# Schematic.net
KiCad netlist of a schematic drawn in Altium Designer
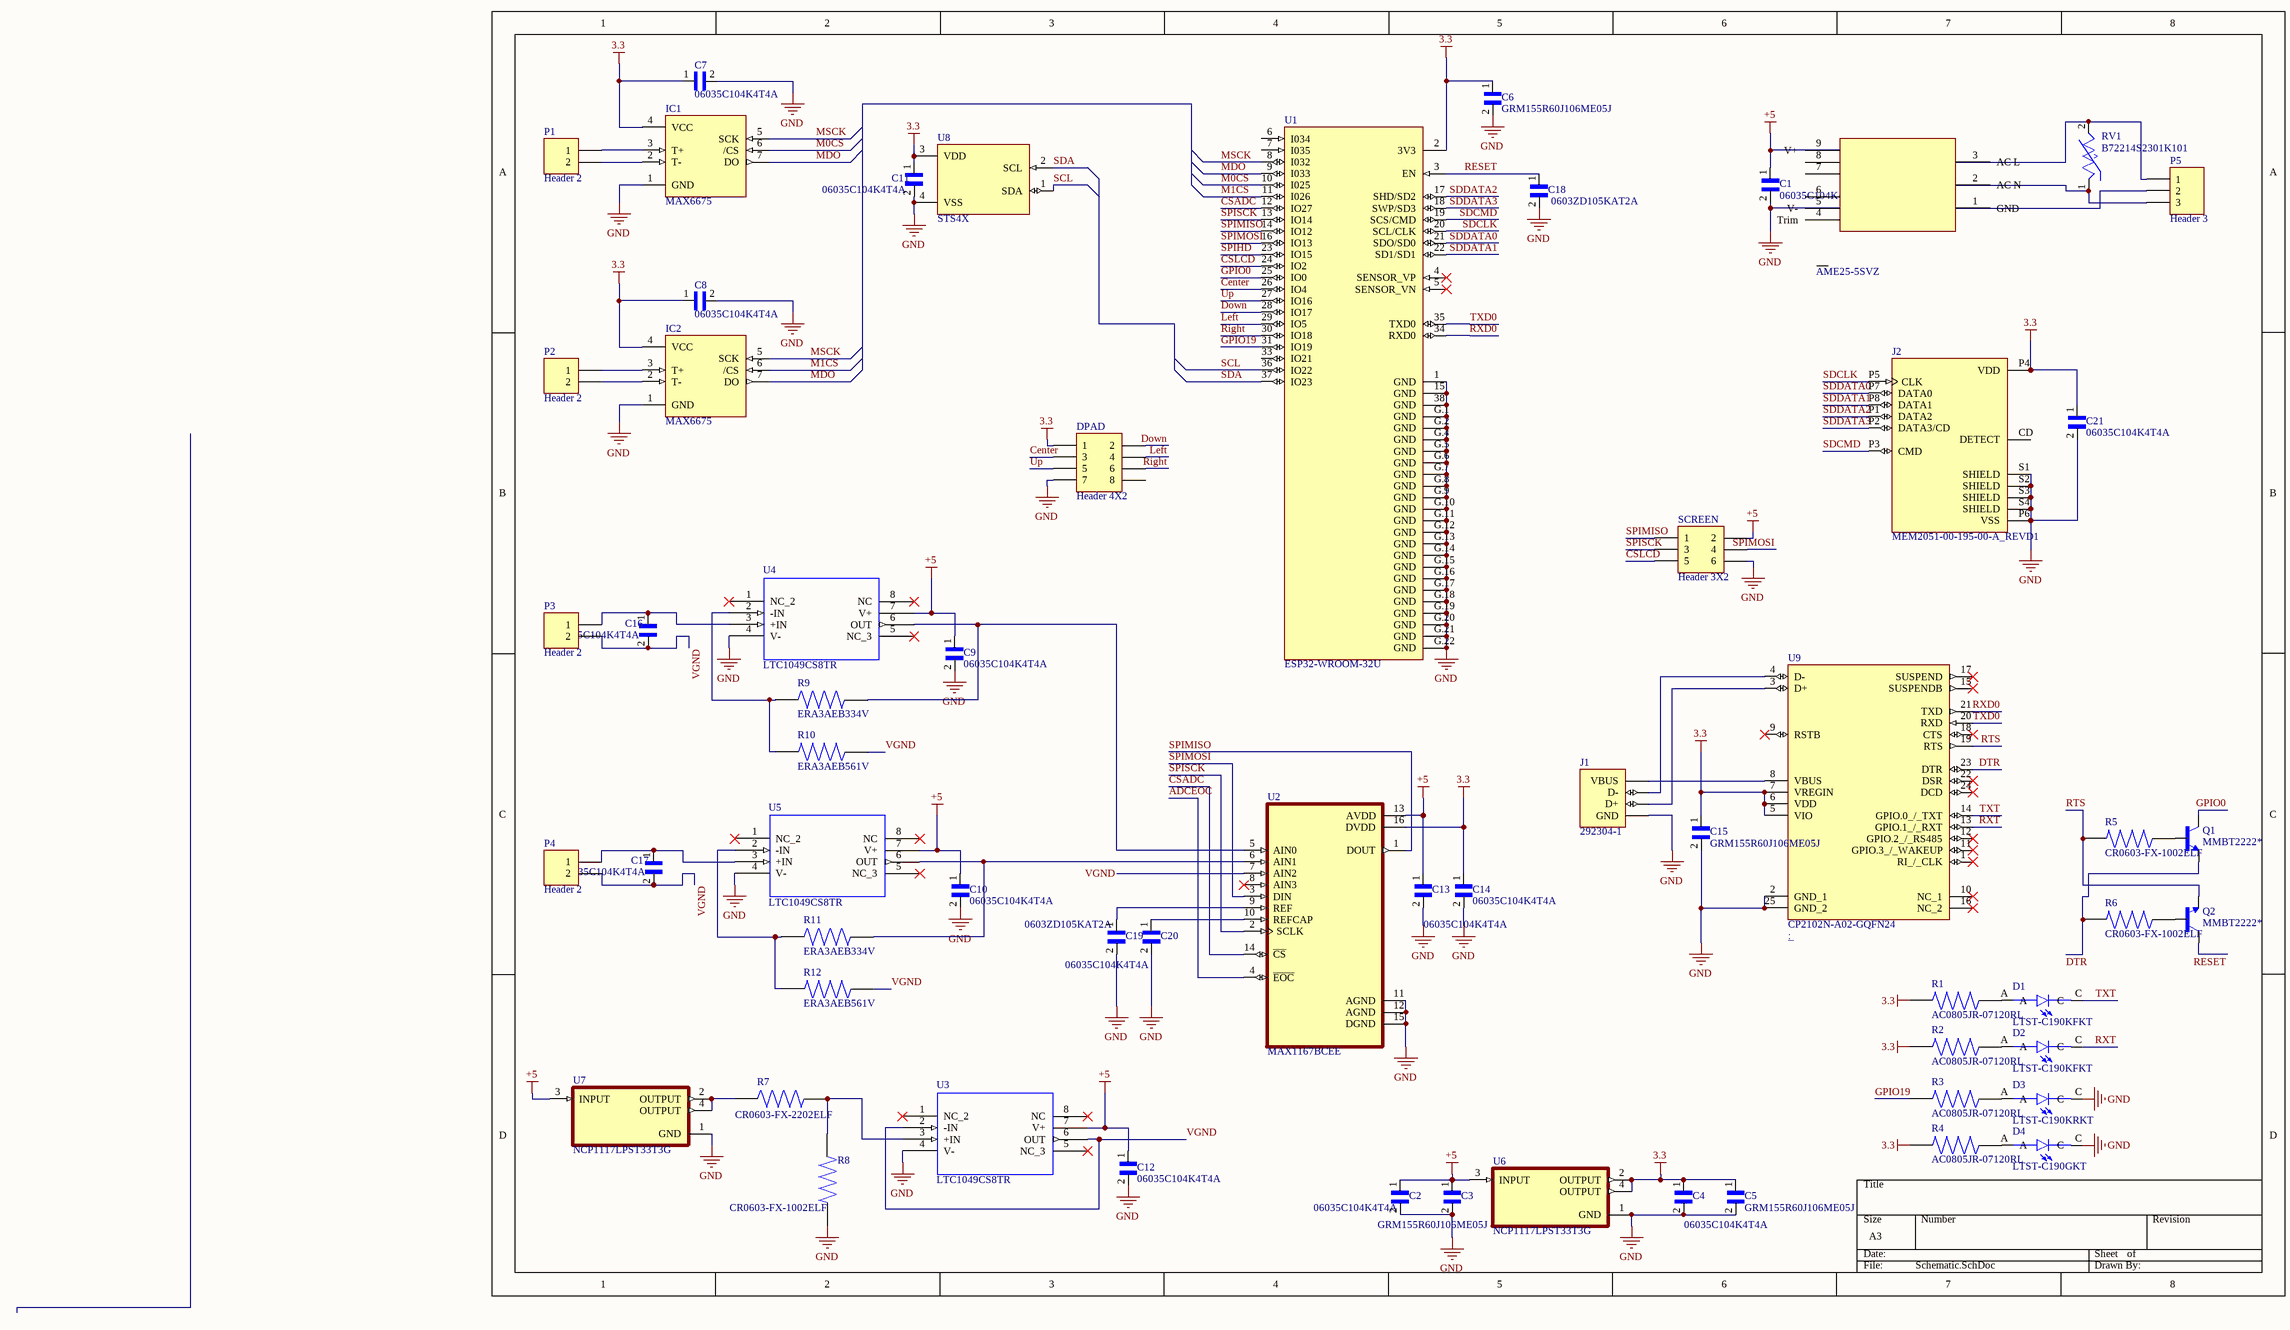
[diagram p0: Schematic.SchDoc]

(export (version "E")
  (design (tool "Eeschema 10.0.6"))
  (components
    (comp (ref "C1")
      (value "06035C104K4T4A")
      (footprint "CAPC1608X90N")
      (description "0.1ÂµF Â±10% 50V Ceramic Capacitor X7R 0603 _1608 Metric_")
      (fields (field (name "DIGI-KEY_PART_NUMBER") "478-9903-1-ND") (field (name "MF") "AVX"))
      (libsource (lib "06035C104K4T4A") (part "06035C104K4T4A"))
    )
    (comp (ref "C2")
      (value "06035C104K4T4A")
      (footprint "CAPC1608X90N")
      (description "0.1ÂµF Â±10% 50V Ceramic Capacitor X7R 0603 _1608 Metric_")
      (fields (field (name "DIGI-KEY_PART_NUMBER") "478-9903-1-ND") (field (name "MF") "AVX"))
      (libsource (lib "06035C104K4T4A") (part "06035C104K4T4A"))
    )
    (comp (ref "C3")
      (value "GRM155R60J106ME05J")
      (footprint "CAPC1005X70N")
      (libsource (lib "GRM155R60J106ME05J") (part "GRM155R60J106ME05J"))
    )
    (comp (ref "C4")
      (value "06035C104K4T4A")
      (footprint "CAPC1608X90N")
      (description "0.1ÂµF Â±10% 50V Ceramic Capacitor X7R 0603 _1608 Metric_")
      (fields (field (name "DIGI-KEY_PART_NUMBER") "478-9903-1-ND") (field (name "MF") "AVX"))
      (libsource (lib "06035C104K4T4A") (part "06035C104K4T4A"))
    )
    (comp (ref "C5")
      (value "GRM155R60J106ME05J")
      (footprint "CAPC1005X70N")
      (libsource (lib "GRM155R60J106ME05J") (part "GRM155R60J106ME05J"))
    )
    (comp (ref "C6")
      (value "GRM155R60J106ME05J")
      (footprint "CAPC1005X70N")
      (libsource (lib "GRM155R60J106ME05J") (part "GRM155R60J106ME05J"))
    )
    (comp (ref "C7")
      (value "06035C104K4T4A")
      (footprint "CAPC1608X90N")
      (description "0.1ÂµF Â±10% 50V Ceramic Capacitor X7R 0603 _1608 Metric_")
      (fields (field (name "DIGI-KEY_PART_NUMBER") "478-9903-1-ND") (field (name "MF") "AVX"))
      (libsource (lib "") (part "06035C104K4T4A_1"))
    )
    (comp (ref "C8")
      (value "06035C104K4T4A")
      (footprint "CAPC1608X90N")
      (description "0.1ÂµF Â±10% 50V Ceramic Capacitor X7R 0603 _1608 Metric_")
      (fields (field (name "DIGI-KEY_PART_NUMBER") "478-9903-1-ND") (field (name "MF") "AVX"))
      (libsource (lib "") (part "06035C104K4T4A_1"))
    )
    (comp (ref "C9")
      (value "06035C104K4T4A")
      (footprint "CAPC1608X90N")
      (description "0.1ÂµF Â±10% 50V Ceramic Capacitor X7R 0603 _1608 Metric_")
      (fields (field (name "DIGI-KEY_PART_NUMBER") "478-9903-1-ND") (field (name "MF") "AVX"))
      (libsource (lib "06035C104K4T4A") (part "06035C104K4T4A"))
    )
    (comp (ref "C10")
      (value "06035C104K4T4A")
      (footprint "CAPC1608X90N")
      (description "0.1ÂµF Â±10% 50V Ceramic Capacitor X7R 0603 _1608 Metric_")
      (fields (field (name "DIGI-KEY_PART_NUMBER") "478-9903-1-ND") (field (name "MF") "AVX"))
      (libsource (lib "06035C104K4T4A") (part "06035C104K4T4A"))
    )
    (comp (ref "C11")
      (value "06035C104K4T4A")
      (footprint "CAPC1608X90N")
      (description "0.1ÂµF Â±10% 50V Ceramic Capacitor X7R 0603 _1608 Metric_")
      (fields (field (name "DIGI-KEY_PART_NUMBER") "478-9903-1-ND") (field (name "MF") "AVX"))
      (libsource (lib "06035C104K4T4A") (part "06035C104K4T4A"))
    )
    (comp (ref "C12")
      (value "06035C104K4T4A")
      (footprint "CAPC1608X90N")
      (description "0.1ÂµF Â±10% 50V Ceramic Capacitor X7R 0603 _1608 Metric_")
      (fields (field (name "DIGI-KEY_PART_NUMBER") "478-9903-1-ND") (field (name "MF") "AVX"))
      (libsource (lib "06035C104K4T4A") (part "06035C104K4T4A"))
    )
    (comp (ref "C13")
      (value "06035C104K4T4A")
      (footprint "CAPC1608X90N")
      (description "0.1ÂµF Â±10% 50V Ceramic Capacitor X7R 0603 _1608 Metric_")
      (fields (field (name "DIGI-KEY_PART_NUMBER") "478-9903-1-ND") (field (name "MF") "AVX"))
      (libsource (lib "06035C104K4T4A") (part "06035C104K4T4A"))
    )
    (comp (ref "C14")
      (value "06035C104K4T4A")
      (footprint "CAPC1608X90N")
      (description "0.1ÂµF Â±10% 50V Ceramic Capacitor X7R 0603 _1608 Metric_")
      (fields (field (name "DIGI-KEY_PART_NUMBER") "478-9903-1-ND") (field (name "MF") "AVX"))
      (libsource (lib "06035C104K4T4A") (part "06035C104K4T4A"))
    )
    (comp (ref "C15")
      (value "GRM155R60J106ME05J")
      (footprint "CAPC1005X70N")
      (libsource (lib "GRM155R60J106ME05J") (part "GRM155R60J106ME05J"))
    )
    (comp (ref "C16")
      (value "06035C104K4T4A")
      (footprint "CAPC1608X90N")
      (description "0.1ÂµF Â±10% 50V Ceramic Capacitor X7R 0603 _1608 Metric_")
      (fields (field (name "DIGI-KEY_PART_NUMBER") "478-9903-1-ND") (field (name "MF") "AVX"))
      (libsource (lib "06035C104K4T4A") (part "06035C104K4T4A"))
    )
    (comp (ref "C17")
      (value "06035C104K4T4A")
      (footprint "CAPC1608X90N")
      (description "0.1ÂµF Â±10% 50V Ceramic Capacitor X7R 0603 _1608 Metric_")
      (fields (field (name "DIGI-KEY_PART_NUMBER") "478-9903-1-ND") (field (name "MF") "AVX"))
      (libsource (lib "06035C104K4T4A") (part "06035C104K4T4A"))
    )
    (comp (ref "C18")
      (value "0603ZD105KAT2A")
      (footprint "CAPC1608X90N")
      (description "Cap Ceramic 1uF 10V X5R 10% SMD 0603 85Â°C Paper T/R")
      (libsource (lib "0603ZD105KAT2A") (part "0603ZD105KAT2A"))
    )
    (comp (ref "C19")
      (value "0603ZD105KAT2A")
      (footprint "CAPC1608X90N")
      (description "Cap Ceramic 1uF 10V X5R 10% SMD 0603 85Â°C Paper T/R")
      (libsource (lib "0603ZD105KAT2A") (part "0603ZD105KAT2A"))
    )
    (comp (ref "C20")
      (value "06035C104K4T4A")
      (footprint "CAPC1608X90N")
      (description "0.1ÂµF Â±10% 50V Ceramic Capacitor X7R 0603 _1608 Metric_")
      (fields (field (name "DIGI-KEY_PART_NUMBER") "478-9903-1-ND") (field (name "MF") "AVX"))
      (libsource (lib "06035C104K4T4A") (part "06035C104K4T4A"))
    )
    (comp (ref "C21")
      (value "06035C104K4T4A")
      (footprint "CAPC1608X90N")
      (description "0.1ÂµF Â±10% 50V Ceramic Capacitor X7R 0603 _1608 Metric_")
      (fields (field (name "DIGI-KEY_PART_NUMBER") "478-9903-1-ND") (field (name "MF") "AVX"))
      (libsource (lib "06035C104K4T4A") (part "06035C104K4T4A"))
    )
    (comp (ref "D1")
      (value "LTST-C190KFKT")
      (footprint "LEDM1608X80")
      (description "Orange 605nm LED Indication - Discrete 2V 0603 (1608 Metric)")
      (fields (field (name "DIGI-KEY_PART_NUMBER") "160-1434-1-ND") (field (name "MF") "Lite-On Inc."))
      (libsource (lib "LTST-C190KFKT") (part "LTST-C190KFKT"))
    )
    (comp (ref "D2")
      (value "LTST-C190KFKT")
      (footprint "LEDM1608X80")
      (description "Orange 605nm LED Indication - Discrete 2V 0603 (1608 Metric)")
      (fields (field (name "DIGI-KEY_PART_NUMBER") "160-1434-1-ND") (field (name "MF") "Lite-On Inc."))
      (libsource (lib "LTST-C190KFKT") (part "LTST-C190KFKT"))
    )
    (comp (ref "D3")
      (value "LTST-C190KRKT")
      (footprint "LEDC1608X35N")
      (description "Red 631nm LED Indication - Discrete 2V 0603 _1608 Metric_")
      (fields (field (name "MF") "Lite-On Inc.") (field (name "DIGI-KEY_PART_NUMBER") "160-1436-1-ND"))
      (libsource (lib "LTST-C190KRKT") (part "LTST-C190KRKT"))
    )
    (comp (ref "D4")
      (value "LTST-C190GKT")
      (footprint "LEDM1608X80")
      (description "Green 569nm LED Indication - Discrete 2.1V 0603 (1608 Metric)")
      (fields (field (name "MF") "Lite-On Inc.") (field (name "DIGI-KEY_PART_NUMBER") "160-1183-1-ND"))
      (libsource (lib "LTST-C190GKT") (part "LTST-C190GKT"))
    )
    (comp (ref "DPAD")
      (value "Header 4X2")
      (footprint "HDR2X4")
      (description "Header, 4-Pin, Dual row")
      (fields (field (name "PUBLISHER") "Altium Limited"))
      (libsource (lib "Miscellaneous Connectors") (part "Header 4X2"))
    )
    (comp (ref "IC1")
      (value "MAX6675")
      (footprint "SO08")
      (description "IC THERMOCOUP TO DGTL 8-SOIC")
      (fields (field (name "MF") "Maxim Integrated"))
      (libsource (lib "MAX6675") (part "MAX6675"))
    )
    (comp (ref "IC2")
      (value "MAX6675")
      (footprint "SO08")
      (description "IC THERMOCOUP TO DGTL 8-SOIC")
      (fields (field (name "MF") "Maxim Integrated"))
      (libsource (lib "MAX6675") (part "MAX6675"))
    )
    (comp (ref "J1")
      (value "292304-1")
      (footprint "TE_292304-1")
      (description "CONN USB RECEPT R/A TYPE B 4POS")
      (libsource (lib "292304-1") (part "292304-1"))
    )
    (comp (ref "J2")
      (value "MEM2051-00-195-00-A_REVD1")
      (footprint "GCT_MEM2051-00-195-00-A_REVD1")
      (libsource (lib "MEM2051-00-195-00-A_REVD1") (part "MEM2051-00-195-00-A_REVD1"))
    )
    (comp (ref "P1")
      (value "Header 2")
      (footprint "HDR1X2")
      (description "Header, 2-Pin")
      (fields (field (name "PUBLISHER") "Altium Limited"))
      (libsource (lib "Miscellaneous Connectors") (part "Header 2"))
    )
    (comp (ref "P2")
      (value "Header 2")
      (footprint "HDR1X2")
      (description "Header, 2-Pin")
      (fields (field (name "PUBLISHER") "Altium Limited"))
      (libsource (lib "Miscellaneous Connectors") (part "Header 2"))
    )
    (comp (ref "P3")
      (value "Header 2")
      (footprint "HDR1X2")
      (description "Header, 2-Pin")
      (fields (field (name "PUBLISHER") "Altium Limited"))
      (libsource (lib "Miscellaneous Connectors") (part "Header 2"))
    )
    (comp (ref "P4")
      (value "Header 2")
      (footprint "HDR1X2")
      (description "Header, 2-Pin")
      (fields (field (name "PUBLISHER") "Altium Limited"))
      (libsource (lib "Miscellaneous Connectors") (part "Header 2"))
    )
    (comp (ref "P5")
      (value "Header 3")
      (footprint "HDR1X3")
      (description "Header, 3-Pin")
      (fields (field (name "PUBLISHER") "Altium Limited"))
      (libsource (lib "Miscellaneous Connectors") (part "Header 3"))
    )
    (comp (ref "PS1")
      (value "AME25-5SVZ")
      (footprint "CONV_KWS5A-5")
      (description "Enclosed AC DC Converters")
      (fields (field (name "MF") "TDK-Lambda Americas Inc") (field (name "MP") "KWS5A-5"))
      (libsource (lib "AME25-5SVZ") (part "AME25-5SVZ"))
    )
    (comp (ref "Q1")
      (value "MMBT2222*")
      (footprint "SOT23-BEC")
      (description "Bipolar _BJT_ Transistor NPN 30V 600mA 250MHz 350mW Surface Mount SOT-23-3")
      (fields (field (name "MF") "ON Semiconductor") (field (name "MP") "MMBT2222"))
      (libsource (lib "MMBT2222_") (part "MMBT2222*"))
    )
    (comp (ref "Q2")
      (value "MMBT2222*")
      (footprint "SOT23-BEC")
      (description "Bipolar _BJT_ Transistor NPN 30V 600mA 250MHz 350mW Surface Mount SOT-23-3")
      (fields (field (name "MF") "ON Semiconductor") (field (name "MP") "MMBT2222"))
      (libsource (lib "") (part "MMBT2222*_1"))
    )
    (comp (ref "R1")
      (value "AC0805JR-07120RL")
      (footprint "RESC2012X60N")
      (description "AC0805 120R 5% 0,125W AUTOMO")
      (libsource (lib "AC0805JR-07120RL") (part "AC0805JR-07120RL"))
    )
    (comp (ref "R2")
      (value "AC0805JR-07120RL")
      (footprint "RESC2012X60N")
      (description "AC0805 120R 5% 0,125W AUTOMO")
      (libsource (lib "AC0805JR-07120RL") (part "AC0805JR-07120RL"))
    )
    (comp (ref "R3")
      (value "AC0805JR-07120RL")
      (footprint "RESC2012X60N")
      (description "AC0805 120R 5% 0,125W AUTOMO")
      (libsource (lib "AC0805JR-07120RL") (part "AC0805JR-07120RL"))
    )
    (comp (ref "R4")
      (value "AC0805JR-07120RL")
      (footprint "RESC2012X60N")
      (description "AC0805 120R 5% 0,125W AUTOMO")
      (libsource (lib "AC0805JR-07120RL") (part "AC0805JR-07120RL"))
    )
    (comp (ref "R5")
      (value "CR0603-FX-1002ELF")
      (footprint "RESC1608X55N")
      (description "10 kOhms Â±1% 0.1W, 1/10W Chip Resistor 0603 _1608 Metric_ Moisture Resistant Thick Film")
      (fields (field (name "MF") "Bourns"))
      (libsource (lib "CR0603-FX-1002ELF") (part "CR0603-FX-1002ELF"))
    )
    (comp (ref "R6")
      (value "CR0603-FX-1002ELF")
      (footprint "RESC1608X55N")
      (description "10 kOhms Â±1% 0.1W, 1/10W Chip Resistor 0603 _1608 Metric_ Moisture Resistant Thick Film")
      (fields (field (name "MF") "Bourns"))
      (libsource (lib "CR0603-FX-1002ELF") (part "CR0603-FX-1002ELF"))
    )
    (comp (ref "R7")
      (value "CR0603-FX-2202ELF")
      (footprint "RESC1608X55N")
      (description "Res Thick Film 0603 22K Ohm 1% 1/10W Â±100ppm/Â°C Molded SMD SMD Paper Tape on Plastic Reel")
      (libsource (lib "CR0603-FX-2202ELF") (part "CR0603-FX-2202ELF"))
    )
    (comp (ref "R8")
      (value "CR0603-FX-1002ELF")
      (footprint "RESC1608X55N")
      (description "10 kOhms Â±1% 0.1W, 1/10W Chip Resistor 0603 _1608 Metric_ Moisture Resistant Thick Film")
      (fields (field (name "MF") "Bourns"))
      (libsource (lib "CR0603-FX-1002ELF") (part "CR0603-FX-1002ELF"))
    )
    (comp (ref "R9")
      (value "ERA3AEB334V")
      (footprint "RES_ERA3AEB334V")
      (libsource (lib "ERA3AEB334V") (part "ERA3AEB334V"))
    )
    (comp (ref "R10")
      (value "ERA3AEB561V")
      (footprint "RES_ERA3AEB561V")
      (libsource (lib "ERA3AEB561V") (part "ERA3AEB561V"))
    )
    (comp (ref "R11")
      (value "ERA3AEB334V")
      (footprint "RES_ERA3AEB334V")
      (libsource (lib "ERA3AEB334V") (part "ERA3AEB334V"))
    )
    (comp (ref "R12")
      (value "ERA3AEB561V")
      (footprint "RES_ERA3AEB561V")
      (libsource (lib "ERA3AEB561V") (part "ERA3AEB561V"))
    )
    (comp (ref "RV1")
      (value "B72214S2301K101")
      (footprint "VAR_B72214S2301K101")
      (fields (field (name "MF") "TDK ELECTRONICS"))
      (libsource (lib "B72214S2301K101") (part "B72214S2301K101"))
    )
    (comp (ref "SCREEN")
      (value "Header 3X2")
      (footprint "HDR2X3")
      (description "Header, 3-Pin, Dual row")
      (fields (field (name "PUBLISHER") "Altium Limited"))
      (libsource (lib "Miscellaneous Connectors") (part "Header 3X2"))
    )
    (comp (ref "U1")
      (value "ESP32-WROOM-32U")
      (footprint "XCVR_ESP32-WROOM-32U")
      (fields (field (name "MF") "Espressif Systems"))
      (libsource (lib "ESP32-WROOM-32U") (part "ESP32-WROOM-32U"))
    )
    (comp (ref "U2")
      (value "MAX1167BCEE")
      (footprint "SOP63P602X175-16N")
      (libsource (lib "MAX1167BCEE") (part "MAX1167BCEE"))
    )
    (comp (ref "U3")
      (value "LTC1049CS8TR")
      (footprint "SO-8_S")
      (libsource (lib "LTC1049CS8TR") (part "LTC1049CS8TR"))
    )
    (comp (ref "U4")
      (value "LTC1049CS8TR")
      (footprint "SO-8_S")
      (libsource (lib "LTC1049CS8TR") (part "LTC1049CS8TR"))
    )
    (comp (ref "U5")
      (value "LTC1049CS8TR")
      (footprint "SO-8_S")
      (libsource (lib "LTC1049CS8TR") (part "LTC1049CS8TR"))
    )
    (comp (ref "U6")
      (value "NCP1117LPST33T3G")
      (footprint "SOT230P700X175-4N")
      (description "Linear Voltage Regulator IC 1 Output 1A SOT-223")
      (fields (field (name "MF") "ON Semiconductor"))
      (libsource (lib "NCP1117LPST33T3G") (part "NCP1117LPST33T3G"))
    )
    (comp (ref "U7")
      (value "NCP1117LPST33T3G")
      (footprint "SOT230P700X175-4N")
      (description "Linear Voltage Regulator IC 1 Output 1A SOT-223")
      (fields (field (name "MF") "ON Semiconductor"))
      (libsource (lib "NCP1117LPST33T3G") (part "NCP1117LPST33T3G"))
    )
    (comp (ref "U8")
      (value "STS4X")
      (footprint "STS4X")
      (description "Digital Temperature Sensor, Â±0.2 Â°C, Ultra-Low-Power, I2C fast mode plus")
      (fields (field (name "MF") "Sensirion") (field (name "MP") "STS40-CD1B-R3"))
      (libsource (lib "STS4X") (part "STS4X"))
    )
    (comp (ref "U9")
      (value "CP2102N-A02-GQFN24")
      (footprint "QFN50P400X400X80-25N")
      (description "USB Bridge, USB to UART USB 2.0 UART Interface 24-QFN (4x4)")
      (fields (field (name "MF") "Silicon Labs"))
      (libsource (lib "CP2102N-A02-GQFN24") (part "CP2102N-A02-GQFN24"))
    )
  )
  (nets
    (net (code "1") (name "+5") (class "Default")
      (node (ref "C1") (pin "1") (pinfunction "1_1") (pintype "passive"))
      (node (ref "C10") (pin "1") (pinfunction "1_1") (pintype "passive"))
      (node (ref "C12") (pin "1") (pinfunction "1_1") (pintype "passive"))
      (node (ref "C13") (pin "1") (pinfunction "1_1") (pintype "passive"))
      (node (ref "C2") (pin "1") (pinfunction "1_1") (pintype "passive"))
      (node (ref "C3") (pin "1") (pinfunction "1_1") (pintype "passive"))
      (node (ref "C9") (pin "1") (pinfunction "1_1") (pintype "passive"))
      (node (ref "PS1") (pin "9") (pinfunction "V+_9") (pintype "passive"))
      (node (ref "SCREEN") (pin "2") (pinfunction "2_2") (pintype "passive"))
      (node (ref "U2") (pin "13") (pinfunction "AVDD_13") (pintype "power_in"))
      (node (ref "U3") (pin "7") (pinfunction "V+_7") (pintype "power_in"))
      (node (ref "U4") (pin "7") (pinfunction "V+_7") (pintype "power_in"))
      (node (ref "U5") (pin "7") (pinfunction "V+_7") (pintype "power_in"))
      (node (ref "U6") (pin "3") (pinfunction "INPUT_3") (pintype "input"))
      (node (ref "U7") (pin "3") (pinfunction "INPUT_3") (pintype "input"))
    )
    (net (code "2") (name "/ADCEOC") (class "Default")
      (node (ref "U2") (pin "4") (pinfunction "~{EOC}_4") (pintype "bidirectional"))
    )
    (net (code "3") (name "/CSADC") (class "Default")
      (node (ref "U1") (pin "12") (pinfunction "IO27_12") (pintype "bidirectional"))
      (node (ref "U2") (pin "14") (pinfunction "~{CS}_14") (pintype "bidirectional"))
    )
    (net (code "4") (name "/CSLCD") (class "Default")
      (node (ref "SCREEN") (pin "5") (pinfunction "5_5") (pintype "passive"))
      (node (ref "U1") (pin "24") (pinfunction "IO2_24") (pintype "bidirectional"))
    )
    (net (code "5") (name "/Center") (class "Default")
      (node (ref "DPAD") (pin "3") (pinfunction "3_3") (pintype "passive"))
      (node (ref "U1") (pin "26") (pinfunction "IO4_26") (pintype "bidirectional"))
    )
    (net (code "6") (name "/DTR") (class "Default")
      (node (ref "Q1") (pin "E") (pinfunction "E_E") (pintype "passive"))
      (node (ref "R6") (pin "2") (pinfunction "2_2") (pintype "passive"))
      (node (ref "U9") (pin "23") (pinfunction "DTR_23") (pintype "bidirectional"))
    )
    (net (code "7") (name "/Down") (class "Default")
      (node (ref "DPAD") (pin "2") (pinfunction "2_2") (pintype "passive"))
      (node (ref "U1") (pin "28") (pinfunction "IO17_28") (pintype "bidirectional"))
    )
    (net (code "8") (name "/GPIO0") (class "Default")
      (node (ref "Q1") (pin "C") (pinfunction "C_C") (pintype "passive"))
      (node (ref "U1") (pin "25") (pinfunction "IO0_25") (pintype "bidirectional"))
    )
    (net (code "9") (name "/GPIO19") (class "Default")
      (node (ref "R3") (pin "2") (pinfunction "2_2") (pintype "passive"))
      (node (ref "U1") (pin "31") (pinfunction "IO19_31") (pintype "bidirectional"))
    )
    (net (code "10") (name "/Left") (class "Default")
      (node (ref "DPAD") (pin "4") (pinfunction "4_4") (pintype "passive"))
      (node (ref "U1") (pin "29") (pinfunction "IO5_29") (pintype "bidirectional"))
    )
    (net (code "11") (name "/M0CS") (class "Default")
      (node (ref "IC1") (pin "6") (pinfunction "/CS_6") (pintype "input"))
      (node (ref "U1") (pin "10") (pinfunction "I025_10") (pintype "bidirectional"))
    )
    (net (code "12") (name "/M1CS") (class "Default")
      (node (ref "IC2") (pin "6") (pinfunction "/CS_6") (pintype "input"))
      (node (ref "U1") (pin "11") (pinfunction "I026_11") (pintype "bidirectional"))
    )
    (net (code "13") (name "/MDO") (class "Default")
      (node (ref "IC1") (pin "7") (pinfunction "DO_7") (pintype "output"))
      (node (ref "IC2") (pin "7") (pinfunction "DO_7") (pintype "output"))
      (node (ref "U1") (pin "9") (pinfunction "I033_9") (pintype "bidirectional"))
    )
    (net (code "14") (name "/MSCK") (class "Default")
      (node (ref "IC1") (pin "5") (pinfunction "SCK_5") (pintype "input"))
      (node (ref "IC2") (pin "5") (pinfunction "SCK_5") (pintype "input"))
      (node (ref "U1") (pin "8") (pinfunction "I032_8") (pintype "bidirectional"))
    )
    (net (code "15") (name "/RESET") (class "Default")
      (node (ref "C18") (pin "1") (pinfunction "1_1") (pintype "passive"))
      (node (ref "Q2") (pin "C") (pinfunction "C_C") (pintype "passive"))
      (node (ref "U1") (pin "3") (pinfunction "EN_3") (pintype "input"))
    )
    (net (code "16") (name "/RTS") (class "Default")
      (node (ref "Q2") (pin "E") (pinfunction "E_E") (pintype "passive"))
      (node (ref "R5") (pin "2") (pinfunction "2_2") (pintype "passive"))
      (node (ref "U9") (pin "19") (pinfunction "RTS_19") (pintype "output"))
    )
    (net (code "17") (name "/RXD0") (class "Default")
      (node (ref "U1") (pin "34") (pinfunction "RXD0_34") (pintype "bidirectional"))
      (node (ref "U9") (pin "21") (pinfunction "TXD_21") (pintype "output"))
    )
    (net (code "18") (name "/RXT") (class "Default")
      (node (ref "D2") (pin "C") (pinfunction "C_C") (pintype "passive"))
      (node (ref "U9") (pin "13") (pinfunction "GPIO.1_/_RXT_13") (pintype "bidirectional"))
    )
    (net (code "19") (name "/Right") (class "Default")
      (node (ref "DPAD") (pin "6") (pinfunction "6_6") (pintype "passive"))
      (node (ref "U1") (pin "30") (pinfunction "IO18_30") (pintype "bidirectional"))
    )
    (net (code "20") (name "/SCL") (class "Default")
      (node (ref "U1") (pin "36") (pinfunction "IO22_36") (pintype "bidirectional"))
      (node (ref "U8") (pin "1") (pinfunction "SDA_1") (pintype "bidirectional"))
    )
    (net (code "21") (name "/SDA") (class "Default")
      (node (ref "U1") (pin "37") (pinfunction "IO23_37") (pintype "bidirectional"))
      (node (ref "U8") (pin "2") (pinfunction "SCL_2") (pintype "input"))
    )
    (net (code "22") (name "/SDCLK") (class "Default")
      (node (ref "J2") (pin "P5") (pinfunction "CLK_P5") (pintype "input"))
      (node (ref "U1") (pin "20") (pinfunction "SCL/CLK_20") (pintype "bidirectional"))
    )
    (net (code "23") (name "/SDCMD") (class "Default")
      (node (ref "J2") (pin "P3") (pinfunction "CMD_P3") (pintype "bidirectional"))
      (node (ref "U1") (pin "19") (pinfunction "SCS/CMD_19") (pintype "bidirectional"))
    )
    (net (code "24") (name "/SDDATA0") (class "Default")
      (node (ref "J2") (pin "P7") (pinfunction "DATA0_P7") (pintype "bidirectional"))
      (node (ref "U1") (pin "21") (pinfunction "SDO/SD0_21") (pintype "bidirectional"))
    )
    (net (code "25") (name "/SDDATA1") (class "Default")
      (node (ref "J2") (pin "P8") (pinfunction "DATA1_P8") (pintype "bidirectional"))
      (node (ref "U1") (pin "22") (pinfunction "SD1/SD1_22") (pintype "bidirectional"))
    )
    (net (code "26") (name "/SDDATA2") (class "Default")
      (node (ref "J2") (pin "P1") (pinfunction "DATA2_P1") (pintype "bidirectional"))
      (node (ref "U1") (pin "17") (pinfunction "SHD/SD2_17") (pintype "bidirectional"))
    )
    (net (code "27") (name "/SDDATA3") (class "Default")
      (node (ref "J2") (pin "P2") (pinfunction "DATA3/CD_P2") (pintype "bidirectional"))
      (node (ref "U1") (pin "18") (pinfunction "SWP/SD3_18") (pintype "bidirectional"))
    )
    (net (code "28") (name "/SPIHD") (class "Default")
      (node (ref "U1") (pin "23") (pinfunction "IO15_23") (pintype "bidirectional"))
    )
    (net (code "29") (name "/SPIMISO") (class "Default")
      (node (ref "SCREEN") (pin "1") (pinfunction "1_1") (pintype "passive"))
      (node (ref "U1") (pin "14") (pinfunction "IO12_14") (pintype "bidirectional"))
      (node (ref "U2") (pin "1") (pinfunction "DOUT_1") (pintype "output"))
    )
    (net (code "30") (name "/SPIMOSI") (class "Default")
      (node (ref "SCREEN") (pin "4") (pinfunction "4_4") (pintype "passive"))
      (node (ref "U1") (pin "16") (pinfunction "IO13_16") (pintype "bidirectional"))
      (node (ref "U2") (pin "3") (pinfunction "DIN_3") (pintype "input"))
    )
    (net (code "31") (name "/SPISCK") (class "Default")
      (node (ref "SCREEN") (pin "3") (pinfunction "3_3") (pintype "passive"))
      (node (ref "U1") (pin "13") (pinfunction "IO14_13") (pintype "bidirectional"))
      (node (ref "U2") (pin "2") (pinfunction "SCLK_2") (pintype "input"))
    )
    (net (code "32") (name "/TXD0") (class "Default")
      (node (ref "U1") (pin "35") (pinfunction "TXD0_35") (pintype "bidirectional"))
      (node (ref "U9") (pin "20") (pinfunction "RXD_20") (pintype "input"))
    )
    (net (code "33") (name "/TXT") (class "Default")
      (node (ref "D1") (pin "C") (pinfunction "C_C") (pintype "passive"))
      (node (ref "U9") (pin "14") (pinfunction "GPIO.0_/_TXT_14") (pintype "bidirectional"))
    )
    (net (code "34") (name "/Up") (class "Default")
      (node (ref "DPAD") (pin "5") (pinfunction "5_5") (pintype "passive"))
      (node (ref "U1") (pin "27") (pinfunction "IO16_27") (pintype "bidirectional"))
    )
    (net (code "35") (name "/VGND") (class "Default")
      (node (ref "C16") (pin "2") (pinfunction "2_2") (pintype "passive"))
      (node (ref "C17") (pin "2") (pinfunction "2_2") (pintype "passive"))
      (node (ref "P3") (pin "2") (pinfunction "2_2") (pintype "passive"))
      (node (ref "P4") (pin "2") (pinfunction "2_2") (pintype "passive"))
      (node (ref "R10") (pin "1") (pinfunction "1_1") (pintype "passive"))
      (node (ref "R12") (pin "1") (pinfunction "1_1") (pintype "passive"))
      (node (ref "U2") (pin "7") (pinfunction "AIN2_7") (pintype "input"))
      (node (ref "U3") (pin "2") (pinfunction "-IN_2") (pintype "input"))
      (node (ref "U3") (pin "6") (pinfunction "OUT_6") (pintype "output"))
    )
    (net (code "36") (name "3.3") (class "Default")
      (node (ref "C11") (pin "1") (pinfunction "1_1") (pintype "passive"))
      (node (ref "C14") (pin "1") (pinfunction "1_1") (pintype "passive"))
      (node (ref "C15") (pin "1") (pinfunction "1_1") (pintype "passive"))
      (node (ref "C21") (pin "1") (pinfunction "1_1") (pintype "passive"))
      (node (ref "C4") (pin "1") (pinfunction "1_1") (pintype "passive"))
      (node (ref "C5") (pin "1") (pinfunction "1_1") (pintype "passive"))
      (node (ref "C6") (pin "1") (pinfunction "1_1") (pintype "passive"))
      (node (ref "C7") (pin "1") (pinfunction "1_1") (pintype "passive"))
      (node (ref "C8") (pin "1") (pinfunction "1_1") (pintype "passive"))
      (node (ref "DPAD") (pin "1") (pinfunction "1_1") (pintype "passive"))
      (node (ref "IC1") (pin "4") (pinfunction "VCC_4") (pintype "power_in"))
      (node (ref "IC2") (pin "4") (pinfunction "VCC_4") (pintype "power_in"))
      (node (ref "J2") (pin "P4") (pinfunction "VDD_P4") (pintype "power_in"))
      (node (ref "R1") (pin "2") (pinfunction "2_2") (pintype "passive"))
      (node (ref "R2") (pin "2") (pinfunction "2_2") (pintype "passive"))
      (node (ref "R4") (pin "2") (pinfunction "2_2") (pintype "passive"))
      (node (ref "U1") (pin "2") (pinfunction "3V3_2") (pintype "power_in"))
      (node (ref "U2") (pin "16") (pinfunction "DVDD_16") (pintype "power_in"))
      (node (ref "U6") (pin "2") (pinfunction "OUTPUT_2") (pintype "output"))
      (node (ref "U6") (pin "4") (pinfunction "OUTPUT_4") (pintype "output"))
      (node (ref "U8") (pin "3") (pinfunction "VDD_3") (pintype "power_in"))
      (node (ref "U9") (pin "5") (pinfunction "VIO_5") (pintype "power_in"))
      (node (ref "U9") (pin "6") (pinfunction "VDD_6") (pintype "power_in"))
      (node (ref "U9") (pin "7") (pinfunction "VREGIN_7") (pintype "power_in"))
    )
    (net (code "37") (name "GND") (class "Default")
      (node (ref "C1") (pin "2") (pinfunction "2_2") (pintype "passive"))
      (node (ref "C10") (pin "2") (pinfunction "2_2") (pintype "passive"))
      (node (ref "C11") (pin "2") (pinfunction "2_2") (pintype "passive"))
      (node (ref "C12") (pin "2") (pinfunction "2_2") (pintype "passive"))
      (node (ref "C13") (pin "2") (pinfunction "2_2") (pintype "passive"))
      (node (ref "C14") (pin "2") (pinfunction "2_2") (pintype "passive"))
      (node (ref "C15") (pin "2") (pinfunction "2_2") (pintype "passive"))
      (node (ref "C18") (pin "2") (pinfunction "2_2") (pintype "passive"))
      (node (ref "C19") (pin "2") (pinfunction "2_2") (pintype "passive"))
      (node (ref "C2") (pin "2") (pinfunction "2_2") (pintype "passive"))
      (node (ref "C20") (pin "2") (pinfunction "2_2") (pintype "passive"))
      (node (ref "C21") (pin "2") (pinfunction "2_2") (pintype "passive"))
      (node (ref "C3") (pin "2") (pinfunction "2_2") (pintype "passive"))
      (node (ref "C4") (pin "2") (pinfunction "2_2") (pintype "passive"))
      (node (ref "C5") (pin "2") (pinfunction "2_2") (pintype "passive"))
      (node (ref "C6") (pin "2") (pinfunction "2_2") (pintype "passive"))
      (node (ref "C7") (pin "2") (pinfunction "2_2") (pintype "passive"))
      (node (ref "C8") (pin "2") (pinfunction "2_2") (pintype "passive"))
      (node (ref "C9") (pin "2") (pinfunction "2_2") (pintype "passive"))
      (node (ref "D3") (pin "C") (pinfunction "C_C") (pintype "passive"))
      (node (ref "D4") (pin "C") (pinfunction "C_C") (pintype "passive"))
      (node (ref "DPAD") (pin "7") (pinfunction "7_7") (pintype "passive"))
      (node (ref "IC1") (pin "1") (pinfunction "GND_1") (pintype "power_in"))
      (node (ref "IC2") (pin "1") (pinfunction "GND_1") (pintype "power_in"))
      (node (ref "J1") (pin "4") (pinfunction "GND_4") (pintype "power_in"))
      (node (ref "J2") (pin "P6") (pinfunction "VSS_P6") (pintype "power_in"))
      (node (ref "J2") (pin "S1") (pinfunction "SHIELD_S1") (pintype "passive"))
      (node (ref "J2") (pin "S2") (pinfunction "SHIELD_S2") (pintype "passive"))
      (node (ref "J2") (pin "S3") (pinfunction "SHIELD_S3") (pintype "passive"))
      (node (ref "J2") (pin "S4") (pinfunction "SHIELD_S4") (pintype "passive"))
      (node (ref "PS1") (pin "5") (pinfunction "V-_5") (pintype "passive"))
      (node (ref "R8") (pin "1") (pinfunction "1_1") (pintype "passive"))
      (node (ref "SCREEN") (pin "6") (pinfunction "6_6") (pintype "passive"))
      (node (ref "U1") (pin "1") (pinfunction "GND_1") (pintype "power_in"))
      (node (ref "U1") (pin "15") (pinfunction "GND_15") (pintype "power_in"))
      (node (ref "U1") (pin "38") (pinfunction "GND_38") (pintype "power_in"))
      (node (ref "U1") (pin "G.1") (pinfunction "GND_G.1") (pintype "power_in"))
      (node (ref "U1") (pin "G.10") (pinfunction "GND_G.10") (pintype "power_in"))
      (node (ref "U1") (pin "G.11") (pinfunction "GND_G.11") (pintype "power_in"))
      (node (ref "U1") (pin "G.12") (pinfunction "GND_G.12") (pintype "power_in"))
      (node (ref "U1") (pin "G.13") (pinfunction "GND_G.13") (pintype "power_in"))
      (node (ref "U1") (pin "G.14") (pinfunction "GND_G.14") (pintype "power_in"))
      (node (ref "U1") (pin "G.15") (pinfunction "GND_G.15") (pintype "power_in"))
      (node (ref "U1") (pin "G.16") (pinfunction "GND_G.16") (pintype "power_in"))
      (node (ref "U1") (pin "G.17") (pinfunction "GND_G.17") (pintype "power_in"))
      (node (ref "U1") (pin "G.18") (pinfunction "GND_G.18") (pintype "power_in"))
      (node (ref "U1") (pin "G.19") (pinfunction "GND_G.19") (pintype "power_in"))
      (node (ref "U1") (pin "G.2") (pinfunction "GND_G.2") (pintype "power_in"))
      (node (ref "U1") (pin "G.20") (pinfunction "GND_G.20") (pintype "power_in"))
      (node (ref "U1") (pin "G.21") (pinfunction "GND_G.21") (pintype "power_in"))
      (node (ref "U1") (pin "G.22") (pinfunction "GND_G.22") (pintype "power_in"))
      (node (ref "U1") (pin "G.4") (pinfunction "GND_G.4") (pintype "power_in"))
      (node (ref "U1") (pin "G.5") (pinfunction "GND_G.5") (pintype "power_in"))
      (node (ref "U1") (pin "G.6") (pinfunction "GND_G.6") (pintype "power_in"))
      (node (ref "U1") (pin "G.7") (pinfunction "GND_G.7") (pintype "power_in"))
      (node (ref "U1") (pin "G.8") (pinfunction "GND_G.8") (pintype "power_in"))
      (node (ref "U1") (pin "G.9") (pinfunction "GND_G.9") (pintype "power_in"))
      (node (ref "U2") (pin "11") (pinfunction "AGND_11") (pintype "power_in"))
      (node (ref "U2") (pin "12") (pinfunction "AGND_12") (pintype "power_in"))
      (node (ref "U2") (pin "15") (pinfunction "DGND_15") (pintype "power_in"))
      (node (ref "U3") (pin "4") (pinfunction "V-_4") (pintype "power_in"))
      (node (ref "U4") (pin "4") (pinfunction "V-_4") (pintype "power_in"))
      (node (ref "U5") (pin "4") (pinfunction "V-_4") (pintype "power_in"))
      (node (ref "U6") (pin "1") (pinfunction "GND_1") (pintype "power_in"))
      (node (ref "U7") (pin "1") (pinfunction "GND_1") (pintype "power_in"))
      (node (ref "U8") (pin "4") (pinfunction "VSS_4") (pintype "power_in"))
      (node (ref "U9") (pin "2") (pinfunction "GND_1_2") (pintype "power_in"))
      (node (ref "U9") (pin "25") (pinfunction "GND_2_25") (pintype "power_in"))
    )
    (net (code "38") (name "Net-(D1-PadA)") (class "Default")
      (node (ref "D1") (pin "A") (pinfunction "A_A") (pintype "passive"))
      (node (ref "R1") (pin "1") (pinfunction "1_1") (pintype "passive"))
    )
    (net (code "39") (name "Net-(D2-PadA)") (class "Default")
      (node (ref "D2") (pin "A") (pinfunction "A_A") (pintype "passive"))
      (node (ref "R2") (pin "1") (pinfunction "1_1") (pintype "passive"))
    )
    (net (code "40") (name "Net-(D3-PadA)") (class "Default")
      (node (ref "D3") (pin "A") (pinfunction "A_A") (pintype "passive"))
      (node (ref "R3") (pin "1") (pinfunction "1_1") (pintype "passive"))
    )
    (net (code "41") (name "Net-(D4-PadA)") (class "Default")
      (node (ref "D4") (pin "A") (pinfunction "A_A") (pintype "passive"))
      (node (ref "R4") (pin "1") (pinfunction "1_1") (pintype "passive"))
    )
    (net (code "42") (name "Net-(IC1-T+)") (class "Default")
      (node (ref "IC1") (pin "3") (pinfunction "T+_3") (pintype "input"))
      (node (ref "P1") (pin "1") (pinfunction "1_1") (pintype "passive"))
    )
    (net (code "43") (name "Net-(IC1-T-)") (class "Default")
      (node (ref "IC1") (pin "2") (pinfunction "T-_2") (pintype "input"))
      (node (ref "P1") (pin "2") (pinfunction "2_2") (pintype "passive"))
    )
    (net (code "44") (name "Net-(IC2-T+)") (class "Default")
      (node (ref "IC2") (pin "3") (pinfunction "T+_3") (pintype "input"))
      (node (ref "P2") (pin "1") (pinfunction "1_1") (pintype "passive"))
    )
    (net (code "45") (name "Net-(IC2-T-)") (class "Default")
      (node (ref "IC2") (pin "2") (pinfunction "T-_2") (pintype "input"))
      (node (ref "P2") (pin "2") (pinfunction "2_2") (pintype "passive"))
    )
    (net (code "46") (name "Net-(J1-D+)") (class "Default")
      (node (ref "J1") (pin "3") (pinfunction "D+_3") (pintype "bidirectional"))
      (node (ref "U9") (pin "3") (pinfunction "D+_3") (pintype "bidirectional"))
    )
    (net (code "47") (name "Net-(J1-D-)") (class "Default")
      (node (ref "J1") (pin "2") (pinfunction "D-_2") (pintype "bidirectional"))
      (node (ref "U9") (pin "4") (pinfunction "D-_4") (pintype "bidirectional"))
    )
    (net (code "48") (name "Net-(J1-VBUS)") (class "Default")
      (node (ref "J1") (pin "1") (pinfunction "VBUS_1") (pintype "power_in"))
      (node (ref "U9") (pin "8") (pinfunction "VBUS_8") (pintype "power_in"))
    )
    (net (code "49") (name "Net-(PS1-AC_L)") (class "Default")
      (node (ref "P5") (pin "1") (pinfunction "1_1") (pintype "passive"))
      (node (ref "PS1") (pin "3") (pinfunction "AC_L_3") (pintype "passive"))
      (node (ref "RV1") (pin "2") (pinfunction "2_2") (pintype "passive"))
    )
    (net (code "50") (name "Net-(PS1-AC_N)") (class "Default")
      (node (ref "P5") (pin "3") (pinfunction "3_3") (pintype "passive"))
      (node (ref "PS1") (pin "2") (pinfunction "AC_N_2") (pintype "passive"))
      (node (ref "RV1") (pin "1") (pinfunction "1_1") (pintype "passive"))
    )
    (net (code "51") (name "Net-(PS1-GND)") (class "Default")
      (node (ref "P5") (pin "2") (pinfunction "2_2") (pintype "passive"))
      (node (ref "PS1") (pin "1") (pinfunction "GND_1") (pintype "passive"))
    )
    (net (code "52") (name "Net-(Q1-PadB)") (class "Default")
      (node (ref "Q1") (pin "B") (pinfunction "B_B") (pintype "passive"))
      (node (ref "R5") (pin "1") (pinfunction "1_1") (pintype "passive"))
    )
    (net (code "53") (name "Net-(Q2-PadB)") (class "Default")
      (node (ref "Q2") (pin "B") (pinfunction "B_B") (pintype "passive"))
      (node (ref "R6") (pin "1") (pinfunction "1_1") (pintype "passive"))
    )
    (net (code "54") (name "Net-(R7-Pad1)") (class "Default")
      (node (ref "R7") (pin "1") (pinfunction "1_1") (pintype "passive"))
      (node (ref "U7") (pin "2") (pinfunction "OUTPUT_2") (pintype "output"))
      (node (ref "U7") (pin "4") (pinfunction "OUTPUT_4") (pintype "output"))
    )
    (net (code "55") (name "Net-(U2-AIN0)") (class "Default")
      (node (ref "R9") (pin "2") (pinfunction "2_2") (pintype "passive"))
      (node (ref "U2") (pin "5") (pinfunction "AIN0_5") (pintype "input"))
      (node (ref "U4") (pin "6") (pinfunction "OUT_6") (pintype "output"))
    )
    (net (code "56") (name "Net-(U2-AIN1)") (class "Default")
      (node (ref "R11") (pin "2") (pinfunction "2_2") (pintype "passive"))
      (node (ref "U2") (pin "6") (pinfunction "AIN1_6") (pintype "input"))
      (node (ref "U5") (pin "6") (pinfunction "OUT_6") (pintype "output"))
    )
    (net (code "57") (name "Net-(U2-REF)") (class "Default")
      (node (ref "C19") (pin "1") (pinfunction "1_1") (pintype "passive"))
      (node (ref "U2") (pin "9") (pinfunction "REF_9") (pintype "input"))
    )
    (net (code "58") (name "Net-(U2-REFCAP)") (class "Default")
      (node (ref "C20") (pin "1") (pinfunction "1_1") (pintype "passive"))
      (node (ref "U2") (pin "10") (pinfunction "REFCAP_10") (pintype "input"))
    )
    (net (code "59") (name "Net-(U3-+IN)") (class "Default")
      (node (ref "R7") (pin "2") (pinfunction "2_2") (pintype "passive"))
      (node (ref "R8") (pin "2") (pinfunction "2_2") (pintype "passive"))
      (node (ref "U3") (pin "3") (pinfunction "+IN_3") (pintype "input"))
    )
    (net (code "60") (name "Net-(U4-+IN)") (class "Default")
      (node (ref "C16") (pin "1") (pinfunction "1_1") (pintype "passive"))
      (node (ref "P3") (pin "1") (pinfunction "1_1") (pintype "passive"))
      (node (ref "U4") (pin "3") (pinfunction "+IN_3") (pintype "input"))
    )
    (net (code "61") (name "Net-(U4--IN)") (class "Default")
      (node (ref "R10") (pin "2") (pinfunction "2_2") (pintype "passive"))
      (node (ref "R9") (pin "1") (pinfunction "1_1") (pintype "passive"))
      (node (ref "U4") (pin "2") (pinfunction "-IN_2") (pintype "input"))
    )
    (net (code "62") (name "Net-(U5-+IN)") (class "Default")
      (node (ref "C17") (pin "1") (pinfunction "1_1") (pintype "passive"))
      (node (ref "P4") (pin "1") (pinfunction "1_1") (pintype "passive"))
      (node (ref "U5") (pin "3") (pinfunction "+IN_3") (pintype "input"))
    )
    (net (code "63") (name "Net-(U5--IN)") (class "Default")
      (node (ref "R11") (pin "1") (pinfunction "1_1") (pintype "passive"))
      (node (ref "R12") (pin "2") (pinfunction "2_2") (pintype "passive"))
      (node (ref "U5") (pin "2") (pinfunction "-IN_2") (pintype "input"))
    )
    (net (code "64") (name "unconnected-(DPAD-Pad8)") (class "Default")
      (node (ref "DPAD") (pin "8") (pinfunction "8_8") (pintype "passive"))
    )
    (net (code "65") (name "unconnected-(J2-DETECT-PadCD)") (class "Default")
      (node (ref "J2") (pin "CD") (pinfunction "DETECT_CD") (pintype "passive"))
    )
    (net (code "66") (name "unconnected-(PS1-Pad6)") (class "Default")
      (node (ref "PS1") (pin "6") (pintype "passive"))
    )
    (net (code "67") (name "unconnected-(PS1-Pad7)") (class "Default")
      (node (ref "PS1") (pin "7") (pintype "passive"))
    )
    (net (code "68") (name "unconnected-(PS1-Pad8)") (class "Default")
      (node (ref "PS1") (pin "8") (pintype "passive"))
    )
    (net (code "69") (name "unconnected-(PS1-Trim-Pad4)") (class "Default")
      (node (ref "PS1") (pin "4") (pinfunction "Trim_4") (pintype "passive"))
    )
    (net (code "70") (name "unconnected-(U1-I034-Pad6)") (class "Default")
      (node (ref "U1") (pin "6") (pinfunction "I034_6") (pintype "input"))
    )
    (net (code "71") (name "unconnected-(U1-I035-Pad7)") (class "Default")
      (node (ref "U1") (pin "7") (pinfunction "I035_7") (pintype "input"))
    )
    (net (code "72") (name "unconnected-(U1-IO21-Pad33)") (class "Default")
      (node (ref "U1") (pin "33") (pinfunction "IO21_33") (pintype "bidirectional"))
    )
    (net (code "73") (name "unconnected-(U1-SENSOR_VN-Pad5)") (class "Default")
      (node (ref "U1") (pin "5") (pinfunction "SENSOR_VN_5") (pintype "input+no_connect"))
    )
    (net (code "74") (name "unconnected-(U1-SENSOR_VP-Pad4)") (class "Default")
      (node (ref "U1") (pin "4") (pinfunction "SENSOR_VP_4") (pintype "input+no_connect"))
    )
    (net (code "75") (name "unconnected-(U2-AIN3-Pad8)") (class "Default")
      (node (ref "U2") (pin "8") (pinfunction "AIN3_8") (pintype "input+no_connect"))
    )
    (net (code "76") (name "unconnected-(U3-NC-Pad8)") (class "Default")
      (node (ref "U3") (pin "8") (pinfunction "NC_8") (pintype "passive+no_connect"))
    )
    (net (code "77") (name "unconnected-(U3-NC_2-Pad1)") (class "Default")
      (node (ref "U3") (pin "1") (pinfunction "NC_2_1") (pintype "passive+no_connect"))
    )
    (net (code "78") (name "unconnected-(U3-NC_3-Pad5)") (class "Default")
      (node (ref "U3") (pin "5") (pinfunction "NC_3_5") (pintype "passive+no_connect"))
    )
    (net (code "79") (name "unconnected-(U4-NC-Pad8)") (class "Default")
      (node (ref "U4") (pin "8") (pinfunction "NC_8") (pintype "passive+no_connect"))
    )
    (net (code "80") (name "unconnected-(U4-NC_2-Pad1)") (class "Default")
      (node (ref "U4") (pin "1") (pinfunction "NC_2_1") (pintype "passive+no_connect"))
    )
    (net (code "81") (name "unconnected-(U4-NC_3-Pad5)") (class "Default")
      (node (ref "U4") (pin "5") (pinfunction "NC_3_5") (pintype "passive+no_connect"))
    )
    (net (code "82") (name "unconnected-(U5-NC-Pad8)") (class "Default")
      (node (ref "U5") (pin "8") (pinfunction "NC_8") (pintype "passive+no_connect"))
    )
    (net (code "83") (name "unconnected-(U5-NC_2-Pad1)") (class "Default")
      (node (ref "U5") (pin "1") (pinfunction "NC_2_1") (pintype "passive+no_connect"))
    )
    (net (code "84") (name "unconnected-(U5-NC_3-Pad5)") (class "Default")
      (node (ref "U5") (pin "5") (pinfunction "NC_3_5") (pintype "passive+no_connect"))
    )
    (net (code "85") (name "unconnected-(U9-CTS-Pad18)") (class "Default")
      (node (ref "U9") (pin "18") (pinfunction "CTS_18") (pintype "bidirectional+no_connect"))
    )
    (net (code "86") (name "unconnected-(U9-DCD-Pad24)") (class "Default")
      (node (ref "U9") (pin "24") (pinfunction "DCD_24") (pintype "bidirectional+no_connect"))
    )
    (net (code "87") (name "unconnected-(U9-DSR-Pad22)") (class "Default")
      (node (ref "U9") (pin "22") (pinfunction "DSR_22") (pintype "bidirectional+no_connect"))
    )
    (net (code "88") (name "unconnected-(U9-GPIO.2_{slash}_RS485-Pad12)") (class "Default")
      (node (ref "U9") (pin "12") (pinfunction "GPIO.2_/_RS485_12") (pintype "bidirectional+no_connect"))
    )
    (net (code "89") (name "unconnected-(U9-GPIO.3_{slash}_WAKEUP-Pad11)") (class "Default")
      (node (ref "U9") (pin "11") (pinfunction "GPIO.3_/_WAKEUP_11") (pintype "bidirectional+no_connect"))
    )
    (net (code "90") (name "unconnected-(U9-NC_1-Pad10)") (class "Default")
      (node (ref "U9") (pin "10") (pinfunction "NC_1_10") (pintype "passive+no_connect"))
    )
    (net (code "91") (name "unconnected-(U9-NC_2-Pad16)") (class "Default")
      (node (ref "U9") (pin "16") (pinfunction "NC_2_16") (pintype "passive+no_connect"))
    )
    (net (code "92") (name "unconnected-(U9-RI_{slash}_CLK-Pad1)") (class "Default")
      (node (ref "U9") (pin "1") (pinfunction "RI_/_CLK_1") (pintype "bidirectional+no_connect"))
    )
    (net (code "93") (name "unconnected-(U9-RSTB-Pad9)") (class "Default")
      (node (ref "U9") (pin "9") (pinfunction "RSTB_9") (pintype "bidirectional+no_connect"))
    )
    (net (code "94") (name "unconnected-(U9-SUSPEND-Pad17)") (class "Default")
      (node (ref "U9") (pin "17") (pinfunction "SUSPEND_17") (pintype "output+no_connect"))
    )
    (net (code "95") (name "unconnected-(U9-SUSPENDB-Pad15)") (class "Default")
      (node (ref "U9") (pin "15") (pinfunction "SUSPENDB_15") (pintype "output+no_connect"))
    )
  )
)
